# design.net
KiCad netlist of a schematic drawn in Altium Designer
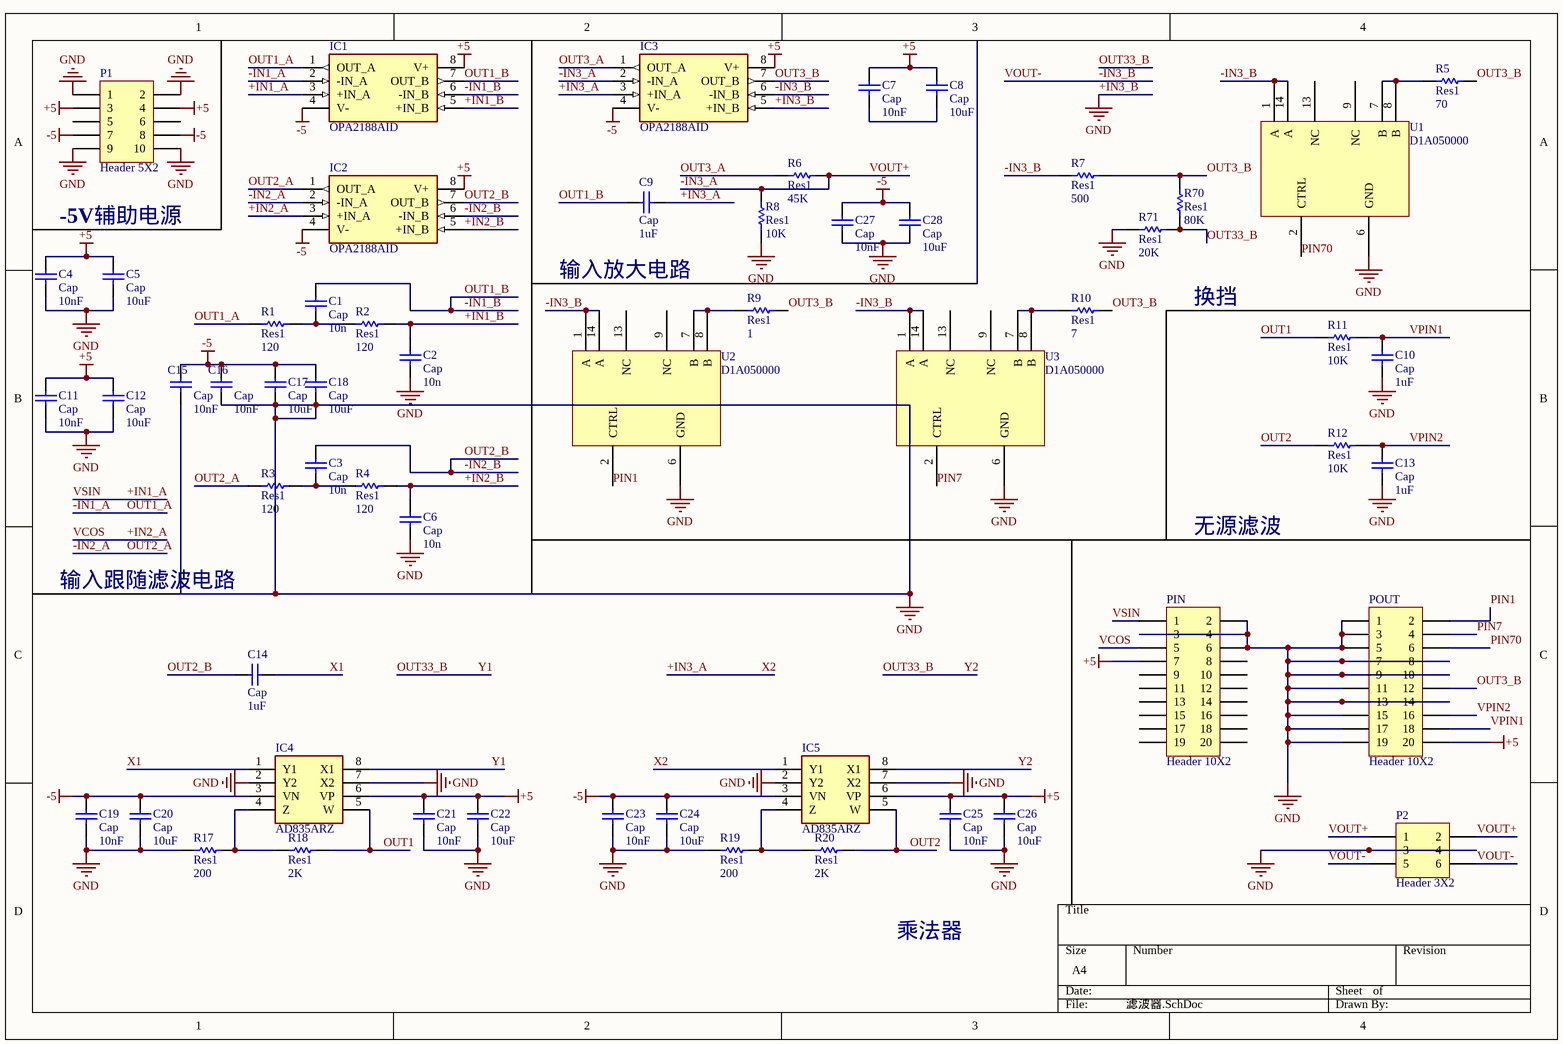
[diagram p0: 滤波器.SchDoc]

(export (version "E")
  (design (tool "Eeschema 10.0.6"))
  (components
    (comp (ref "C1")
      (value "Cap")
      (footprint "1608[0603]")
      (description "Capacitor")
      (fields (field (name "ALTIUM_VALUE") "10n") (field (name "PUBLISHER") "Altium Limited"))
      (libsource (lib "Miscellaneous Devices") (part "Cap"))
    )
    (comp (ref "C2")
      (value "Cap")
      (footprint "1608[0603]")
      (description "Capacitor")
      (fields (field (name "ALTIUM_VALUE") "10n") (field (name "PUBLISHER") "Altium Limited"))
      (libsource (lib "Miscellaneous Devices") (part "Cap"))
    )
    (comp (ref "C3")
      (value "Cap")
      (footprint "1608[0603]")
      (description "Capacitor")
      (fields (field (name "ALTIUM_VALUE") "10n") (field (name "PUBLISHER") "Altium Limited"))
      (libsource (lib "Miscellaneous Devices") (part "Cap"))
    )
    (comp (ref "C4")
      (value "Cap")
      (footprint "1608[0603]")
      (description "Capacitor")
      (fields (field (name "ALTIUM_VALUE") "10nF") (field (name "PUBLISHER") "Altium Limited"))
      (libsource (lib "Miscellaneous Devices") (part "Cap"))
    )
    (comp (ref "C5")
      (value "Cap")
      (footprint "1608[0603]")
      (description "Capacitor")
      (fields (field (name "ALTIUM_VALUE") "10uF") (field (name "PUBLISHER") "Altium Limited"))
      (libsource (lib "Miscellaneous Devices") (part "Cap"))
    )
    (comp (ref "C6")
      (value "Cap")
      (footprint "1608[0603]")
      (description "Capacitor")
      (fields (field (name "ALTIUM_VALUE") "10n") (field (name "PUBLISHER") "Altium Limited"))
      (libsource (lib "Miscellaneous Devices") (part "Cap"))
    )
    (comp (ref "C7")
      (value "Cap")
      (footprint "1608[0603]")
      (description "Capacitor")
      (fields (field (name "ALTIUM_VALUE") "10nF") (field (name "PUBLISHER") "Altium Limited"))
      (libsource (lib "Miscellaneous Devices") (part "Cap"))
    )
    (comp (ref "C8")
      (value "Cap")
      (footprint "1608[0603]")
      (description "Capacitor")
      (fields (field (name "ALTIUM_VALUE") "10uF") (field (name "PUBLISHER") "Altium Limited"))
      (libsource (lib "Miscellaneous Devices") (part "Cap"))
    )
    (comp (ref "C9")
      (value "Cap")
      (footprint "1608[0603]")
      (description "Capacitor")
      (fields (field (name "ALTIUM_VALUE") "1uF") (field (name "PUBLISHER") "Altium Limited"))
      (libsource (lib "Miscellaneous Devices") (part "Cap"))
    )
    (comp (ref "C10")
      (value "Cap")
      (footprint "C1210")
      (description "Capacitor")
      (fields (field (name "ALTIUM_VALUE") "1uF") (field (name "PUBLISHER") "Altium Limited"))
      (libsource (lib "Miscellaneous Devices") (part "Cap"))
    )
    (comp (ref "C11")
      (value "Cap")
      (footprint "1608[0603]")
      (description "Capacitor")
      (fields (field (name "ALTIUM_VALUE") "10nF") (field (name "PUBLISHER") "Altium Limited"))
      (libsource (lib "Miscellaneous Devices") (part "Cap"))
    )
    (comp (ref "C12")
      (value "Cap")
      (footprint "1608[0603]")
      (description "Capacitor")
      (fields (field (name "ALTIUM_VALUE") "10uF") (field (name "PUBLISHER") "Altium Limited"))
      (libsource (lib "Miscellaneous Devices") (part "Cap"))
    )
    (comp (ref "C13")
      (value "Cap")
      (footprint "C1210")
      (description "Capacitor")
      (fields (field (name "ALTIUM_VALUE") "1uF") (field (name "PUBLISHER") "Altium Limited"))
      (libsource (lib "Miscellaneous Devices") (part "Cap"))
    )
    (comp (ref "C14")
      (value "Cap")
      (footprint "AXIAL-0.3")
      (description "Capacitor")
      (fields (field (name "ALTIUM_VALUE") "1uF") (field (name "PUBLISHER") "Altium Limited"))
      (libsource (lib "Miscellaneous Devices") (part "Cap"))
    )
    (comp (ref "C15")
      (value "Cap")
      (footprint "1608[0603]")
      (description "Capacitor")
      (fields (field (name "ALTIUM_VALUE") "10nF") (field (name "PUBLISHER") "Altium Limited"))
      (libsource (lib "Miscellaneous Devices") (part "Cap"))
    )
    (comp (ref "C16")
      (value "Cap")
      (footprint "1608[0603]")
      (description "Capacitor")
      (fields (field (name "ALTIUM_VALUE") "10nF") (field (name "PUBLISHER") "Altium Limited"))
      (libsource (lib "Miscellaneous Devices") (part "Cap"))
    )
    (comp (ref "C17")
      (value "Cap")
      (footprint "1608[0603]")
      (description "Capacitor")
      (fields (field (name "ALTIUM_VALUE") "10uF") (field (name "PUBLISHER") "Altium Limited"))
      (libsource (lib "Miscellaneous Devices") (part "Cap"))
    )
    (comp (ref "C18")
      (value "Cap")
      (footprint "1608[0603]")
      (description "Capacitor")
      (fields (field (name "ALTIUM_VALUE") "10uF") (field (name "PUBLISHER") "Altium Limited"))
      (libsource (lib "Miscellaneous Devices") (part "Cap"))
    )
    (comp (ref "C19")
      (value "Cap")
      (footprint "1608[0603]")
      (description "Capacitor")
      (fields (field (name "ALTIUM_VALUE") "10nF") (field (name "PUBLISHER") "Altium Limited"))
      (libsource (lib "Miscellaneous Devices") (part "Cap"))
    )
    (comp (ref "C20")
      (value "Cap")
      (footprint "1608[0603]")
      (description "Capacitor")
      (fields (field (name "ALTIUM_VALUE") "10uF") (field (name "PUBLISHER") "Altium Limited"))
      (libsource (lib "Miscellaneous Devices") (part "Cap"))
    )
    (comp (ref "C21")
      (value "Cap")
      (footprint "1608[0603]")
      (description "Capacitor")
      (fields (field (name "ALTIUM_VALUE") "10nF") (field (name "PUBLISHER") "Altium Limited"))
      (libsource (lib "Miscellaneous Devices") (part "Cap"))
    )
    (comp (ref "C22")
      (value "Cap")
      (footprint "1608[0603]")
      (description "Capacitor")
      (fields (field (name "ALTIUM_VALUE") "10uF") (field (name "PUBLISHER") "Altium Limited"))
      (libsource (lib "Miscellaneous Devices") (part "Cap"))
    )
    (comp (ref "C23")
      (value "Cap")
      (footprint "1608[0603]")
      (description "Capacitor")
      (fields (field (name "ALTIUM_VALUE") "10nF") (field (name "PUBLISHER") "Altium Limited"))
      (libsource (lib "Miscellaneous Devices") (part "Cap"))
    )
    (comp (ref "C24")
      (value "Cap")
      (footprint "1608[0603]")
      (description "Capacitor")
      (fields (field (name "ALTIUM_VALUE") "10uF") (field (name "PUBLISHER") "Altium Limited"))
      (libsource (lib "Miscellaneous Devices") (part "Cap"))
    )
    (comp (ref "C25")
      (value "Cap")
      (footprint "1608[0603]")
      (description "Capacitor")
      (fields (field (name "ALTIUM_VALUE") "10nF") (field (name "PUBLISHER") "Altium Limited"))
      (libsource (lib "Miscellaneous Devices") (part "Cap"))
    )
    (comp (ref "C26")
      (value "Cap")
      (footprint "1608[0603]")
      (description "Capacitor")
      (fields (field (name "ALTIUM_VALUE") "10uF") (field (name "PUBLISHER") "Altium Limited"))
      (libsource (lib "Miscellaneous Devices") (part "Cap"))
    )
    (comp (ref "C27")
      (value "Cap")
      (footprint "1608[0603]")
      (description "Capacitor")
      (fields (field (name "ALTIUM_VALUE") "10nF") (field (name "PUBLISHER") "Altium Limited"))
      (libsource (lib "Miscellaneous Devices") (part "Cap"))
    )
    (comp (ref "C28")
      (value "Cap")
      (footprint "1608[0603]")
      (description "Capacitor")
      (fields (field (name "ALTIUM_VALUE") "10uF") (field (name "PUBLISHER") "Altium Limited"))
      (libsource (lib "Miscellaneous Devices") (part "Cap"))
    )
    (comp (ref "IC1")
      (value "OPA2188AID")
      (footprint "dip-8")
      (description "Integrated Circuit")
      (fields (field (name "MOUSER PART NUMBER") "595-OPA2188AID") (field (name "RS PART NUMBER") "8122568P"))
      (libsource (lib "*") (part "OPA2188AID"))
    )
    (comp (ref "IC2")
      (value "OPA2188AID")
      (footprint "dip-8")
      (description "Integrated Circuit")
      (fields (field (name "MOUSER PART NUMBER") "595-OPA2188AID") (field (name "RS PART NUMBER") "8122568P"))
      (libsource (lib "*") (part "OPA2188AID"))
    )
    (comp (ref "IC3")
      (value "OPA2188AID")
      (footprint "dip-8")
      (description "Integrated Circuit")
      (fields (field (name "MOUSER PART NUMBER") "595-OPA2188AID") (field (name "RS PART NUMBER") "8122568P"))
      (libsource (lib "*") (part "OPA2188AID"))
    )
    (comp (ref "IC4")
      (value "AD835ARZ")
      (footprint "DIP-8")
      (description "Integrated Circuit")
      (fields (field (name "MOUSER PART NUMBER") "584-AD835ARZ") (field (name "RS PART NUMBER") "5236973"))
      (libsource (lib "*") (part "AD835ARZ"))
    )
    (comp (ref "IC5")
      (value "AD835ARZ")
      (footprint "DIP-8")
      (description "Integrated Circuit")
      (fields (field (name "MOUSER PART NUMBER") "584-AD835ARZ") (field (name "RS PART NUMBER") "5236973"))
      (libsource (lib "*") (part "AD835ARZ"))
    )
    (comp (ref "P1")
      (value "Header 5X2")
      (footprint "HDR2X5")
      (description "Header, 5-Pin, Dual row")
      (fields (field (name "PUBLISHER") "Altium Limited"))
      (libsource (lib "Miscellaneous Connectors") (part "Header 5X2"))
    )
    (comp (ref "P2")
      (value "Header 3X2")
      (footprint "HDR2X3")
      (description "Header, 3-Pin, Dual row")
      (fields (field (name "PUBLISHER") "Altium Limited"))
      (libsource (lib "Miscellaneous Connectors") (part "Header 3X2"))
    )
    (comp (ref "PIN")
      (value "Header 10X2")
      (footprint "HDR2X10")
      (description "Header, 10-Pin, Dual row")
      (fields (field (name "PUBLISHER") "Altium Limited"))
      (libsource (lib "Miscellaneous Connectors") (part "Header 10X2"))
    )
    (comp (ref "POUT")
      (value "Header 10X2")
      (footprint "HDR2X10")
      (description "Header, 10-Pin, Dual row")
      (fields (field (name "PUBLISHER") "Altium Limited"))
      (libsource (lib "Miscellaneous Connectors") (part "Header 10X2"))
    )
    (comp (ref "R1")
      (value "Res1")
      (footprint "1608[0603]")
      (description "Resistor")
      (fields (field (name "ALTIUM_VALUE") "120") (field (name "PUBLISHER") "Altium Limited"))
      (libsource (lib "Miscellaneous Devices") (part "Res1"))
    )
    (comp (ref "R2")
      (value "Res1")
      (footprint "1608[0603]")
      (description "Resistor")
      (fields (field (name "ALTIUM_VALUE") "120") (field (name "PUBLISHER") "Altium Limited"))
      (libsource (lib "Miscellaneous Devices") (part "Res1"))
    )
    (comp (ref "R3")
      (value "Res1")
      (footprint "1608[0603]")
      (description "Resistor")
      (fields (field (name "ALTIUM_VALUE") "120") (field (name "PUBLISHER") "Altium Limited"))
      (libsource (lib "Miscellaneous Devices") (part "Res1"))
    )
    (comp (ref "R4")
      (value "Res1")
      (footprint "1608[0603]")
      (description "Resistor")
      (fields (field (name "ALTIUM_VALUE") "120") (field (name "PUBLISHER") "Altium Limited"))
      (libsource (lib "Miscellaneous Devices") (part "Res1"))
    )
    (comp (ref "R5")
      (value "Res1")
      (footprint "1608[0603]")
      (description "Resistor")
      (fields (field (name "ALTIUM_VALUE") "70") (field (name "PUBLISHER") "Altium Limited"))
      (libsource (lib "Miscellaneous Devices") (part "Res1"))
    )
    (comp (ref "R6")
      (value "Res1")
      (footprint "1608[0603]")
      (description "Resistor")
      (fields (field (name "ALTIUM_VALUE") "45K") (field (name "PUBLISHER") "Altium Limited"))
      (libsource (lib "Miscellaneous Devices") (part "Res1"))
    )
    (comp (ref "R7")
      (value "Res1")
      (footprint "1608[0603]")
      (description "Resistor")
      (fields (field (name "ALTIUM_VALUE") "500") (field (name "PUBLISHER") "Altium Limited"))
      (libsource (lib "Miscellaneous Devices") (part "Res1"))
    )
    (comp (ref "R8")
      (value "Res1")
      (footprint "1608[0603]")
      (description "Resistor")
      (fields (field (name "ALTIUM_VALUE") "10K") (field (name "PUBLISHER") "Altium Limited"))
      (libsource (lib "Miscellaneous Devices") (part "Res1"))
    )
    (comp (ref "R9")
      (value "Res1")
      (footprint "1608[0603]")
      (description "Resistor")
      (fields (field (name "ALTIUM_VALUE") "1") (field (name "PUBLISHER") "Altium Limited"))
      (libsource (lib "Miscellaneous Devices") (part "Res1"))
    )
    (comp (ref "R10")
      (value "Res1")
      (footprint "1608[0603]")
      (description "Resistor")
      (fields (field (name "ALTIUM_VALUE") "7") (field (name "PUBLISHER") "Altium Limited"))
      (libsource (lib "Miscellaneous Devices") (part "Res1"))
    )
    (comp (ref "R11")
      (value "Res1")
      (footprint "C1210")
      (description "Resistor")
      (fields (field (name "ALTIUM_VALUE") "10K") (field (name "PUBLISHER") "Altium Limited"))
      (libsource (lib "Miscellaneous Devices") (part "Res1"))
    )
    (comp (ref "R12")
      (value "Res1")
      (footprint "C1210")
      (description "Resistor")
      (fields (field (name "ALTIUM_VALUE") "10K") (field (name "PUBLISHER") "Altium Limited"))
      (libsource (lib "Miscellaneous Devices") (part "Res1"))
    )
    (comp (ref "R17")
      (value "Res1")
      (footprint "1608[0603]")
      (description "Resistor")
      (fields (field (name "ALTIUM_VALUE") "200") (field (name "PUBLISHER") "Altium Limited"))
      (libsource (lib "Miscellaneous Devices") (part "Res1"))
    )
    (comp (ref "R18")
      (value "Res1")
      (footprint "1608[0603]")
      (description "Resistor")
      (fields (field (name "ALTIUM_VALUE") "2K") (field (name "PUBLISHER") "Altium Limited"))
      (libsource (lib "Miscellaneous Devices") (part "Res1"))
    )
    (comp (ref "R19")
      (value "Res1")
      (footprint "1608[0603]")
      (description "Resistor")
      (fields (field (name "ALTIUM_VALUE") "200") (field (name "PUBLISHER") "Altium Limited"))
      (libsource (lib "Miscellaneous Devices") (part "Res1"))
    )
    (comp (ref "R20")
      (value "Res1")
      (footprint "1608[0603]")
      (description "Resistor")
      (fields (field (name "ALTIUM_VALUE") "2K") (field (name "PUBLISHER") "Altium Limited"))
      (libsource (lib "Miscellaneous Devices") (part "Res1"))
    )
    (comp (ref "R70")
      (value "Res1")
      (footprint "1608[0603]")
      (description "Resistor")
      (fields (field (name "ALTIUM_VALUE") "80K") (field (name "PUBLISHER") "Altium Limited"))
      (libsource (lib "Miscellaneous Devices") (part "Res1"))
    )
    (comp (ref "R71")
      (value "Res1")
      (footprint "1608[0603]")
      (description "Resistor")
      (fields (field (name "ALTIUM_VALUE") "20K") (field (name "PUBLISHER") "Altium Limited"))
      (libsource (lib "Miscellaneous Devices") (part "Res1"))
    )
    (comp (ref "U1")
      (value "D1A050000")
      (footprint "D1A050000")
      (libsource (lib "SamacSys") (part "D1A050000"))
    )
    (comp (ref "U2")
      (value "D1A050000")
      (footprint "D1A050000")
      (libsource (lib "SamacSys") (part "D1A050000"))
    )
    (comp (ref "U3")
      (value "D1A050000")
      (footprint "D1A050000")
      (libsource (lib "SamacSys") (part "D1A050000"))
    )
  )
  (nets
    (net (code "1") (name "+5") (class "Default")
      (node (ref "C11") (pin "1") (pinfunction "1_1") (pintype "passive"))
      (node (ref "C12") (pin "1") (pinfunction "1_1") (pintype "passive"))
      (node (ref "C21") (pin "1") (pinfunction "1_1") (pintype "passive"))
      (node (ref "C22") (pin "1") (pinfunction "1_1") (pintype "passive"))
      (node (ref "C25") (pin "1") (pinfunction "1_1") (pintype "passive"))
      (node (ref "C26") (pin "1") (pinfunction "1_1") (pintype "passive"))
      (node (ref "C4") (pin "1") (pinfunction "1_1") (pintype "passive"))
      (node (ref "C5") (pin "1") (pinfunction "1_1") (pintype "passive"))
      (node (ref "C7") (pin "1") (pinfunction "1_1") (pintype "passive"))
      (node (ref "C8") (pin "1") (pinfunction "1_1") (pintype "passive"))
      (node (ref "IC1") (pin "8") (pinfunction "V+_8") (pintype "power_in"))
      (node (ref "IC2") (pin "8") (pinfunction "V+_8") (pintype "power_in"))
      (node (ref "IC3") (pin "8") (pinfunction "V+_8") (pintype "power_in"))
      (node (ref "IC4") (pin "6") (pinfunction "VP_6") (pintype "passive"))
      (node (ref "IC5") (pin "6") (pinfunction "VP_6") (pintype "passive"))
      (node (ref "P1") (pin "3") (pinfunction "3_3") (pintype "passive"))
      (node (ref "P1") (pin "4") (pinfunction "4_4") (pintype "passive"))
      (node (ref "PIN") (pin "7") (pinfunction "7_7") (pintype "passive"))
      (node (ref "POUT") (pin "20") (pinfunction "20_20") (pintype "passive"))
    )
    (net (code "2") (name "-5") (class "Default")
      (node (ref "C15") (pin "1") (pinfunction "1_1") (pintype "passive"))
      (node (ref "C16") (pin "1") (pinfunction "1_1") (pintype "passive"))
      (node (ref "C17") (pin "1") (pinfunction "1_1") (pintype "passive"))
      (node (ref "C18") (pin "1") (pinfunction "1_1") (pintype "passive"))
      (node (ref "C19") (pin "1") (pinfunction "1_1") (pintype "passive"))
      (node (ref "C20") (pin "1") (pinfunction "1_1") (pintype "passive"))
      (node (ref "C23") (pin "1") (pinfunction "1_1") (pintype "passive"))
      (node (ref "C24") (pin "1") (pinfunction "1_1") (pintype "passive"))
      (node (ref "C27") (pin "1") (pinfunction "1_1") (pintype "passive"))
      (node (ref "C28") (pin "1") (pinfunction "1_1") (pintype "passive"))
      (node (ref "IC1") (pin "4") (pinfunction "V-_4") (pintype "power_in"))
      (node (ref "IC2") (pin "4") (pinfunction "V-_4") (pintype "power_in"))
      (node (ref "IC3") (pin "4") (pinfunction "V-_4") (pintype "power_in"))
      (node (ref "IC4") (pin "3") (pinfunction "VN_3") (pintype "passive"))
      (node (ref "IC5") (pin "3") (pinfunction "VN_3") (pintype "passive"))
      (node (ref "P1") (pin "7") (pinfunction "7_7") (pintype "passive"))
      (node (ref "P1") (pin "8") (pinfunction "8_8") (pintype "passive"))
    )
    (net (code "3") (name "/+IN1_A") (class "Default")
      (node (ref "IC1") (pin "3") (pinfunction "+IN_A_3") (pintype "input"))
      (node (ref "PIN") (pin "1") (pinfunction "1_1") (pintype "passive"))
    )
    (net (code "4") (name "/+IN1_B") (class "Default")
      (node (ref "C2") (pin "2") (pinfunction "2_2") (pintype "passive"))
      (node (ref "IC1") (pin "5") (pinfunction "+IN_B_5") (pintype "input"))
      (node (ref "R2") (pin "2") (pinfunction "2_2") (pintype "passive"))
    )
    (net (code "5") (name "/+IN2_A") (class "Default")
      (node (ref "IC2") (pin "3") (pinfunction "+IN_A_3") (pintype "input"))
      (node (ref "PIN") (pin "5") (pinfunction "5_5") (pintype "passive"))
    )
    (net (code "6") (name "/+IN2_B") (class "Default")
      (node (ref "C6") (pin "2") (pinfunction "2_2") (pintype "passive"))
      (node (ref "IC2") (pin "5") (pinfunction "+IN_B_5") (pintype "input"))
      (node (ref "R4") (pin "2") (pinfunction "2_2") (pintype "passive"))
    )
    (net (code "7") (name "/+IN3_A") (class "Default")
      (node (ref "C9") (pin "1") (pinfunction "1_1") (pintype "passive"))
      (node (ref "IC3") (pin "3") (pinfunction "+IN_A_3") (pintype "input"))
      (node (ref "IC5") (pin "1") (pinfunction "Y1_1") (pintype "passive"))
    )
    (net (code "8") (name "/-IN1_A") (class "Default")
      (node (ref "IC1") (pin "1") (pinfunction "OUT_A_1") (pintype "output"))
      (node (ref "IC1") (pin "2") (pinfunction "-IN_A_2") (pintype "input"))
      (node (ref "R1") (pin "1") (pinfunction "1_1") (pintype "passive"))
    )
    (net (code "9") (name "/-IN1_B") (class "Default")
      (node (ref "C1") (pin "2") (pinfunction "2_2") (pintype "passive"))
      (node (ref "C9") (pin "2") (pinfunction "2_2") (pintype "passive"))
      (node (ref "IC1") (pin "6") (pinfunction "-IN_B_6") (pintype "input"))
      (node (ref "IC1") (pin "7") (pinfunction "OUT_B_7") (pintype "output"))
    )
    (net (code "10") (name "/-IN2_A") (class "Default")
      (node (ref "IC2") (pin "1") (pinfunction "OUT_A_1") (pintype "output"))
      (node (ref "IC2") (pin "2") (pinfunction "-IN_A_2") (pintype "input"))
      (node (ref "R3") (pin "1") (pinfunction "1_1") (pintype "passive"))
    )
    (net (code "11") (name "/-IN2_B") (class "Default")
      (node (ref "C14") (pin "2") (pinfunction "2_2") (pintype "passive"))
      (node (ref "C3") (pin "2") (pinfunction "2_2") (pintype "passive"))
      (node (ref "IC2") (pin "6") (pinfunction "-IN_B_6") (pintype "input"))
      (node (ref "IC2") (pin "7") (pinfunction "OUT_B_7") (pintype "output"))
    )
    (net (code "12") (name "/-IN3_A") (class "Default")
      (node (ref "IC3") (pin "2") (pinfunction "-IN_A_2") (pintype "input"))
      (node (ref "P2") (pin "1") (pinfunction "1_1") (pintype "passive"))
      (node (ref "P2") (pin "2") (pinfunction "2_2") (pintype "passive"))
      (node (ref "R6") (pin "1") (pinfunction "1_1") (pintype "passive"))
      (node (ref "R8") (pin "2") (pinfunction "2_2") (pintype "passive"))
    )
    (net (code "13") (name "/-IN3_B") (class "Default")
      (node (ref "IC3") (pin "6") (pinfunction "-IN_B_6") (pintype "input"))
      (node (ref "P2") (pin "5") (pinfunction "5_5") (pintype "passive"))
      (node (ref "P2") (pin "6") (pinfunction "6_6") (pintype "passive"))
      (node (ref "R7") (pin "1") (pinfunction "1_1") (pintype "passive"))
      (node (ref "U1") (pin "1") (pinfunction "A_1") (pintype "passive"))
      (node (ref "U1") (pin "14") (pinfunction "A_14") (pintype "passive"))
      (node (ref "U2") (pin "1") (pinfunction "A_1") (pintype "passive"))
      (node (ref "U2") (pin "14") (pinfunction "A_14") (pintype "passive"))
      (node (ref "U3") (pin "1") (pinfunction "A_1") (pintype "passive"))
      (node (ref "U3") (pin "14") (pinfunction "A_14") (pintype "passive"))
    )
    (net (code "14") (name "/OUT1") (class "Default")
      (node (ref "IC4") (pin "5") (pinfunction "W_5") (pintype "passive"))
      (node (ref "R11") (pin "1") (pinfunction "1_1") (pintype "passive"))
      (node (ref "R18") (pin "2") (pinfunction "2_2") (pintype "passive"))
    )
    (net (code "15") (name "/OUT2") (class "Default")
      (node (ref "IC5") (pin "5") (pinfunction "W_5") (pintype "passive"))
      (node (ref "R12") (pin "1") (pinfunction "1_1") (pintype "passive"))
      (node (ref "R20") (pin "2") (pinfunction "2_2") (pintype "passive"))
    )
    (net (code "16") (name "/OUT3_A") (class "Default")
      (node (ref "IC3") (pin "1") (pinfunction "OUT_A_1") (pintype "output"))
      (node (ref "R6") (pin "2") (pinfunction "2_2") (pintype "passive"))
    )
    (net (code "17") (name "/OUT3_B") (class "Default")
      (node (ref "IC3") (pin "7") (pinfunction "OUT_B_7") (pintype "output"))
      (node (ref "POUT") (pin "12") (pinfunction "12_12") (pintype "passive"))
      (node (ref "R10") (pin "2") (pinfunction "2_2") (pintype "passive"))
      (node (ref "R5") (pin "2") (pinfunction "2_2") (pintype "passive"))
      (node (ref "R7") (pin "2") (pinfunction "2_2") (pintype "passive"))
      (node (ref "R70") (pin "2") (pinfunction "2_2") (pintype "passive"))
      (node (ref "R9") (pin "2") (pinfunction "2_2") (pintype "passive"))
    )
    (net (code "18") (name "/OUT33_B") (class "Default")
      (node (ref "IC4") (pin "8") (pinfunction "X1_8") (pintype "passive"))
      (node (ref "IC5") (pin "8") (pinfunction "X1_8") (pintype "passive"))
      (node (ref "R70") (pin "1") (pinfunction "1_1") (pintype "passive"))
      (node (ref "R71") (pin "1") (pinfunction "1_1") (pintype "passive"))
    )
    (net (code "19") (name "/PIN1") (class "Default")
      (node (ref "POUT") (pin "2") (pinfunction "2_2") (pintype "passive"))
      (node (ref "U2") (pin "2") (pinfunction "CTRL_2") (pintype "passive"))
    )
    (net (code "20") (name "/PIN7") (class "Default")
      (node (ref "POUT") (pin "4") (pinfunction "4_4") (pintype "passive"))
      (node (ref "U3") (pin "2") (pinfunction "CTRL_2") (pintype "passive"))
    )
    (net (code "21") (name "/PIN70") (class "Default")
      (node (ref "POUT") (pin "6") (pinfunction "6_6") (pintype "passive"))
      (node (ref "U1") (pin "2") (pinfunction "CTRL_2") (pintype "passive"))
    )
    (net (code "22") (name "/VPIN1") (class "Default")
      (node (ref "C10") (pin "1") (pinfunction "1_1") (pintype "passive"))
      (node (ref "POUT") (pin "18") (pinfunction "18_18") (pintype "passive"))
      (node (ref "R11") (pin "2") (pinfunction "2_2") (pintype "passive"))
    )
    (net (code "23") (name "/VPIN2") (class "Default")
      (node (ref "C13") (pin "1") (pinfunction "1_1") (pintype "passive"))
      (node (ref "POUT") (pin "16") (pinfunction "16_16") (pintype "passive"))
      (node (ref "R12") (pin "2") (pinfunction "2_2") (pintype "passive"))
    )
    (net (code "24") (name "/X1") (class "Default")
      (node (ref "C14") (pin "1") (pinfunction "1_1") (pintype "passive"))
      (node (ref "IC4") (pin "1") (pinfunction "Y1_1") (pintype "passive"))
    )
    (net (code "25") (name "GND") (class "Default")
      (node (ref "C10") (pin "2") (pinfunction "2_2") (pintype "passive"))
      (node (ref "C11") (pin "2") (pinfunction "2_2") (pintype "passive"))
      (node (ref "C12") (pin "2") (pinfunction "2_2") (pintype "passive"))
      (node (ref "C13") (pin "2") (pinfunction "2_2") (pintype "passive"))
      (node (ref "C15") (pin "2") (pinfunction "2_2") (pintype "passive"))
      (node (ref "C16") (pin "2") (pinfunction "2_2") (pintype "passive"))
      (node (ref "C17") (pin "2") (pinfunction "2_2") (pintype "passive"))
      (node (ref "C18") (pin "2") (pinfunction "2_2") (pintype "passive"))
      (node (ref "C19") (pin "2") (pinfunction "2_2") (pintype "passive"))
      (node (ref "C2") (pin "1") (pinfunction "1_1") (pintype "passive"))
      (node (ref "C20") (pin "2") (pinfunction "2_2") (pintype "passive"))
      (node (ref "C21") (pin "2") (pinfunction "2_2") (pintype "passive"))
      (node (ref "C22") (pin "2") (pinfunction "2_2") (pintype "passive"))
      (node (ref "C23") (pin "2") (pinfunction "2_2") (pintype "passive"))
      (node (ref "C24") (pin "2") (pinfunction "2_2") (pintype "passive"))
      (node (ref "C25") (pin "2") (pinfunction "2_2") (pintype "passive"))
      (node (ref "C26") (pin "2") (pinfunction "2_2") (pintype "passive"))
      (node (ref "C27") (pin "2") (pinfunction "2_2") (pintype "passive"))
      (node (ref "C28") (pin "2") (pinfunction "2_2") (pintype "passive"))
      (node (ref "C4") (pin "2") (pinfunction "2_2") (pintype "passive"))
      (node (ref "C5") (pin "2") (pinfunction "2_2") (pintype "passive"))
      (node (ref "C6") (pin "1") (pinfunction "1_1") (pintype "passive"))
      (node (ref "IC3") (pin "5") (pinfunction "+IN_B_5") (pintype "input"))
      (node (ref "IC4") (pin "2") (pinfunction "Y2_2") (pintype "passive"))
      (node (ref "IC4") (pin "7") (pinfunction "X2_7") (pintype "passive"))
      (node (ref "IC5") (pin "2") (pinfunction "Y2_2") (pintype "passive"))
      (node (ref "IC5") (pin "7") (pinfunction "X2_7") (pintype "passive"))
      (node (ref "P1") (pin "1") (pinfunction "1_1") (pintype "passive"))
      (node (ref "P1") (pin "10") (pinfunction "10_10") (pintype "passive"))
      (node (ref "P1") (pin "2") (pinfunction "2_2") (pintype "passive"))
      (node (ref "P1") (pin "9") (pinfunction "9_9") (pintype "passive"))
      (node (ref "P2") (pin "3") (pinfunction "3_3") (pintype "passive"))
      (node (ref "P2") (pin "4") (pinfunction "4_4") (pintype "passive"))
      (node (ref "PIN") (pin "2") (pinfunction "2_2") (pintype "passive"))
      (node (ref "PIN") (pin "3") (pinfunction "3_3") (pintype "passive"))
      (node (ref "PIN") (pin "4") (pinfunction "4_4") (pintype "passive"))
      (node (ref "PIN") (pin "6") (pinfunction "6_6") (pintype "passive"))
      (node (ref "POUT") (pin "1") (pinfunction "1_1") (pintype "passive"))
      (node (ref "POUT") (pin "10") (pinfunction "10_10") (pintype "passive"))
      (node (ref "POUT") (pin "11") (pinfunction "11_11") (pintype "passive"))
      (node (ref "POUT") (pin "13") (pinfunction "13_13") (pintype "passive"))
      (node (ref "POUT") (pin "14") (pinfunction "14_14") (pintype "passive"))
      (node (ref "POUT") (pin "15") (pinfunction "15_15") (pintype "passive"))
      (node (ref "POUT") (pin "17") (pinfunction "17_17") (pintype "passive"))
      (node (ref "POUT") (pin "19") (pinfunction "19_19") (pintype "passive"))
      (node (ref "POUT") (pin "3") (pinfunction "3_3") (pintype "passive"))
      (node (ref "POUT") (pin "5") (pinfunction "5_5") (pintype "passive"))
      (node (ref "POUT") (pin "7") (pinfunction "7_7") (pintype "passive"))
      (node (ref "POUT") (pin "8") (pinfunction "8_8") (pintype "passive"))
      (node (ref "POUT") (pin "9") (pinfunction "9_9") (pintype "passive"))
      (node (ref "R17") (pin "1") (pinfunction "1_1") (pintype "passive"))
      (node (ref "R19") (pin "1") (pinfunction "1_1") (pintype "passive"))
      (node (ref "R71") (pin "2") (pinfunction "2_2") (pintype "passive"))
      (node (ref "R8") (pin "1") (pinfunction "1_1") (pintype "passive"))
      (node (ref "U1") (pin "6") (pinfunction "GND_6") (pintype "passive"))
      (node (ref "U2") (pin "6") (pinfunction "GND_6") (pintype "passive"))
      (node (ref "U3") (pin "6") (pinfunction "GND_6") (pintype "passive"))
    )
    (net (code "26") (name "Net-(C1-Pad1)") (class "Default")
      (node (ref "C1") (pin "1") (pinfunction "1_1") (pintype "passive"))
      (node (ref "R1") (pin "2") (pinfunction "2_2") (pintype "passive"))
      (node (ref "R2") (pin "1") (pinfunction "1_1") (pintype "passive"))
    )
    (net (code "27") (name "Net-(C3-Pad1)") (class "Default")
      (node (ref "C3") (pin "1") (pinfunction "1_1") (pintype "passive"))
      (node (ref "R3") (pin "2") (pinfunction "2_2") (pintype "passive"))
      (node (ref "R4") (pin "1") (pinfunction "1_1") (pintype "passive"))
    )
    (net (code "28") (name "Net-(C7-Pad2)") (class "Default")
      (node (ref "C7") (pin "2") (pinfunction "2_2") (pintype "passive"))
      (node (ref "C8") (pin "2") (pinfunction "2_2") (pintype "passive"))
    )
    (net (code "29") (name "Net-(IC4-Z)") (class "Default")
      (node (ref "IC4") (pin "4") (pinfunction "Z_4") (pintype "passive"))
      (node (ref "R17") (pin "2") (pinfunction "2_2") (pintype "passive"))
      (node (ref "R18") (pin "1") (pinfunction "1_1") (pintype "passive"))
    )
    (net (code "30") (name "Net-(IC5-Z)") (class "Default")
      (node (ref "IC5") (pin "4") (pinfunction "Z_4") (pintype "passive"))
      (node (ref "R19") (pin "2") (pinfunction "2_2") (pintype "passive"))
      (node (ref "R20") (pin "1") (pinfunction "1_1") (pintype "passive"))
    )
    (net (code "31") (name "Net-(R5-Pad1)") (class "Default")
      (node (ref "R5") (pin "1") (pinfunction "1_1") (pintype "passive"))
      (node (ref "U1") (pin "7") (pinfunction "B_7") (pintype "passive"))
      (node (ref "U1") (pin "8") (pinfunction "B_8") (pintype "passive"))
    )
    (net (code "32") (name "Net-(R9-Pad1)") (class "Default")
      (node (ref "R9") (pin "1") (pinfunction "1_1") (pintype "passive"))
      (node (ref "U2") (pin "7") (pinfunction "B_7") (pintype "passive"))
      (node (ref "U2") (pin "8") (pinfunction "B_8") (pintype "passive"))
    )
    (net (code "33") (name "Net-(R10-Pad1)") (class "Default")
      (node (ref "R10") (pin "1") (pinfunction "1_1") (pintype "passive"))
      (node (ref "U3") (pin "7") (pinfunction "B_7") (pintype "passive"))
      (node (ref "U3") (pin "8") (pinfunction "B_8") (pintype "passive"))
    )
    (net (code "34") (name "unconnected-(P1-Pad5)") (class "Default")
      (node (ref "P1") (pin "5") (pinfunction "5_5") (pintype "passive"))
    )
    (net (code "35") (name "unconnected-(P1-Pad6)") (class "Default")
      (node (ref "P1") (pin "6") (pinfunction "6_6") (pintype "passive"))
    )
    (net (code "36") (name "unconnected-(PIN-Pad8)") (class "Default")
      (node (ref "PIN") (pin "8") (pinfunction "8_8") (pintype "passive"))
    )
    (net (code "37") (name "unconnected-(PIN-Pad9)") (class "Default")
      (node (ref "PIN") (pin "9") (pinfunction "9_9") (pintype "passive"))
    )
    (net (code "38") (name "unconnected-(PIN-Pad10)") (class "Default")
      (node (ref "PIN") (pin "10") (pinfunction "10_10") (pintype "passive"))
    )
    (net (code "39") (name "unconnected-(PIN-Pad11)") (class "Default")
      (node (ref "PIN") (pin "11") (pinfunction "11_11") (pintype "passive"))
    )
    (net (code "40") (name "unconnected-(PIN-Pad12)") (class "Default")
      (node (ref "PIN") (pin "12") (pinfunction "12_12") (pintype "passive"))
    )
    (net (code "41") (name "unconnected-(PIN-Pad13)") (class "Default")
      (node (ref "PIN") (pin "13") (pinfunction "13_13") (pintype "passive"))
    )
    (net (code "42") (name "unconnected-(PIN-Pad14)") (class "Default")
      (node (ref "PIN") (pin "14") (pinfunction "14_14") (pintype "passive"))
    )
    (net (code "43") (name "unconnected-(PIN-Pad15)") (class "Default")
      (node (ref "PIN") (pin "15") (pinfunction "15_15") (pintype "passive"))
    )
    (net (code "44") (name "unconnected-(PIN-Pad16)") (class "Default")
      (node (ref "PIN") (pin "16") (pinfunction "16_16") (pintype "passive"))
    )
    (net (code "45") (name "unconnected-(PIN-Pad17)") (class "Default")
      (node (ref "PIN") (pin "17") (pinfunction "17_17") (pintype "passive"))
    )
    (net (code "46") (name "unconnected-(PIN-Pad18)") (class "Default")
      (node (ref "PIN") (pin "18") (pinfunction "18_18") (pintype "passive"))
    )
    (net (code "47") (name "unconnected-(PIN-Pad19)") (class "Default")
      (node (ref "PIN") (pin "19") (pinfunction "19_19") (pintype "passive"))
    )
    (net (code "48") (name "unconnected-(PIN-Pad20)") (class "Default")
      (node (ref "PIN") (pin "20") (pinfunction "20_20") (pintype "passive"))
    )
    (net (code "49") (name "unconnected-(U1-NC-Pad9)") (class "Default")
      (node (ref "U1") (pin "9") (pinfunction "NC_9") (pintype "passive"))
    )
    (net (code "50") (name "unconnected-(U1-NC-Pad13)") (class "Default")
      (node (ref "U1") (pin "13") (pinfunction "NC_13") (pintype "passive"))
    )
    (net (code "51") (name "unconnected-(U2-NC-Pad9)") (class "Default")
      (node (ref "U2") (pin "9") (pinfunction "NC_9") (pintype "passive"))
    )
    (net (code "52") (name "unconnected-(U2-NC-Pad13)") (class "Default")
      (node (ref "U2") (pin "13") (pinfunction "NC_13") (pintype "passive"))
    )
    (net (code "53") (name "unconnected-(U3-NC-Pad9)") (class "Default")
      (node (ref "U3") (pin "9") (pinfunction "NC_9") (pintype "passive"))
    )
    (net (code "54") (name "unconnected-(U3-NC-Pad13)") (class "Default")
      (node (ref "U3") (pin "13") (pinfunction "NC_13") (pintype "passive"))
    )
  )
)
